# TrafficLightHeaderBoard.net
KiCad netlist of a schematic drawn in Altium Designer
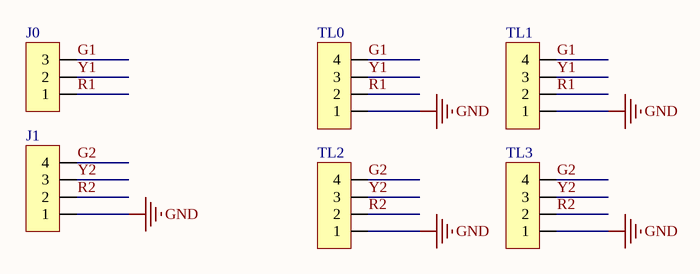
[diagram p0: TrafficLightHeaderBoard.SchDoc]

(export (version "E")
  (design (tool "Eeschema 10.0.6"))
  (components
    (comp (ref "J0")
      (value "Header 3")
      (footprint "Header 3")
      (description "Header, 3-Pin")
      (libsource (lib "BKIT4U_LIB") (part "Header 3"))
    )
    (comp (ref "J1")
      (value "Header 4")
      (footprint "Header 4")
      (description "Header, 4-Pin")
      (libsource (lib "BKIT4U_LIB") (part "Header 4"))
    )
    (comp (ref "TL0")
      (value "Header 4")
      (footprint "Header 4")
      (description "Header, 4-Pin")
      (libsource (lib "BKIT4U_LIB") (part "Header 4"))
    )
    (comp (ref "TL1")
      (value "Header 4")
      (footprint "Header 4")
      (description "Header, 4-Pin")
      (libsource (lib "BKIT4U_LIB") (part "Header 4"))
    )
    (comp (ref "TL2")
      (value "Header 4")
      (footprint "Header 4")
      (description "Header, 4-Pin")
      (libsource (lib "BKIT4U_LIB") (part "Header 4"))
    )
    (comp (ref "TL3")
      (value "Header 4")
      (footprint "Header 4")
      (description "Header, 4-Pin")
      (libsource (lib "BKIT4U_LIB") (part "Header 4"))
    )
  )
  (nets
    (net (code "1") (name "/G1") (class "Default")
      (node (ref "J0") (pin "3") (pinfunction "3_3") (pintype "passive"))
      (node (ref "TL0") (pin "4") (pinfunction "4_4") (pintype "passive"))
      (node (ref "TL1") (pin "4") (pinfunction "4_4") (pintype "passive"))
    )
    (net (code "2") (name "/G2") (class "Default")
      (node (ref "J1") (pin "4") (pinfunction "4_4") (pintype "passive"))
      (node (ref "TL2") (pin "4") (pinfunction "4_4") (pintype "passive"))
      (node (ref "TL3") (pin "4") (pinfunction "4_4") (pintype "passive"))
    )
    (net (code "3") (name "/R1") (class "Default")
      (node (ref "J0") (pin "1") (pinfunction "1_1") (pintype "passive"))
      (node (ref "TL0") (pin "2") (pinfunction "2_2") (pintype "passive"))
      (node (ref "TL1") (pin "2") (pinfunction "2_2") (pintype "passive"))
    )
    (net (code "4") (name "/R2") (class "Default")
      (node (ref "J1") (pin "2") (pinfunction "2_2") (pintype "passive"))
      (node (ref "TL2") (pin "2") (pinfunction "2_2") (pintype "passive"))
      (node (ref "TL3") (pin "2") (pinfunction "2_2") (pintype "passive"))
    )
    (net (code "5") (name "/Y1") (class "Default")
      (node (ref "J0") (pin "2") (pinfunction "2_2") (pintype "passive"))
      (node (ref "TL0") (pin "3") (pinfunction "3_3") (pintype "passive"))
      (node (ref "TL1") (pin "3") (pinfunction "3_3") (pintype "passive"))
    )
    (net (code "6") (name "/Y2") (class "Default")
      (node (ref "J1") (pin "3") (pinfunction "3_3") (pintype "passive"))
      (node (ref "TL2") (pin "3") (pinfunction "3_3") (pintype "passive"))
      (node (ref "TL3") (pin "3") (pinfunction "3_3") (pintype "passive"))
    )
    (net (code "7") (name "GND") (class "Default")
      (node (ref "J1") (pin "1") (pinfunction "1_1") (pintype "passive"))
      (node (ref "TL0") (pin "1") (pinfunction "1_1") (pintype "passive"))
      (node (ref "TL1") (pin "1") (pinfunction "1_1") (pintype "passive"))
      (node (ref "TL2") (pin "1") (pinfunction "1_1") (pintype "passive"))
      (node (ref "TL3") (pin "1") (pinfunction "1_1") (pintype "passive"))
    )
  )
)
